# CurrentSensor.net
KiCad netlist of a schematic drawn in EAGLE
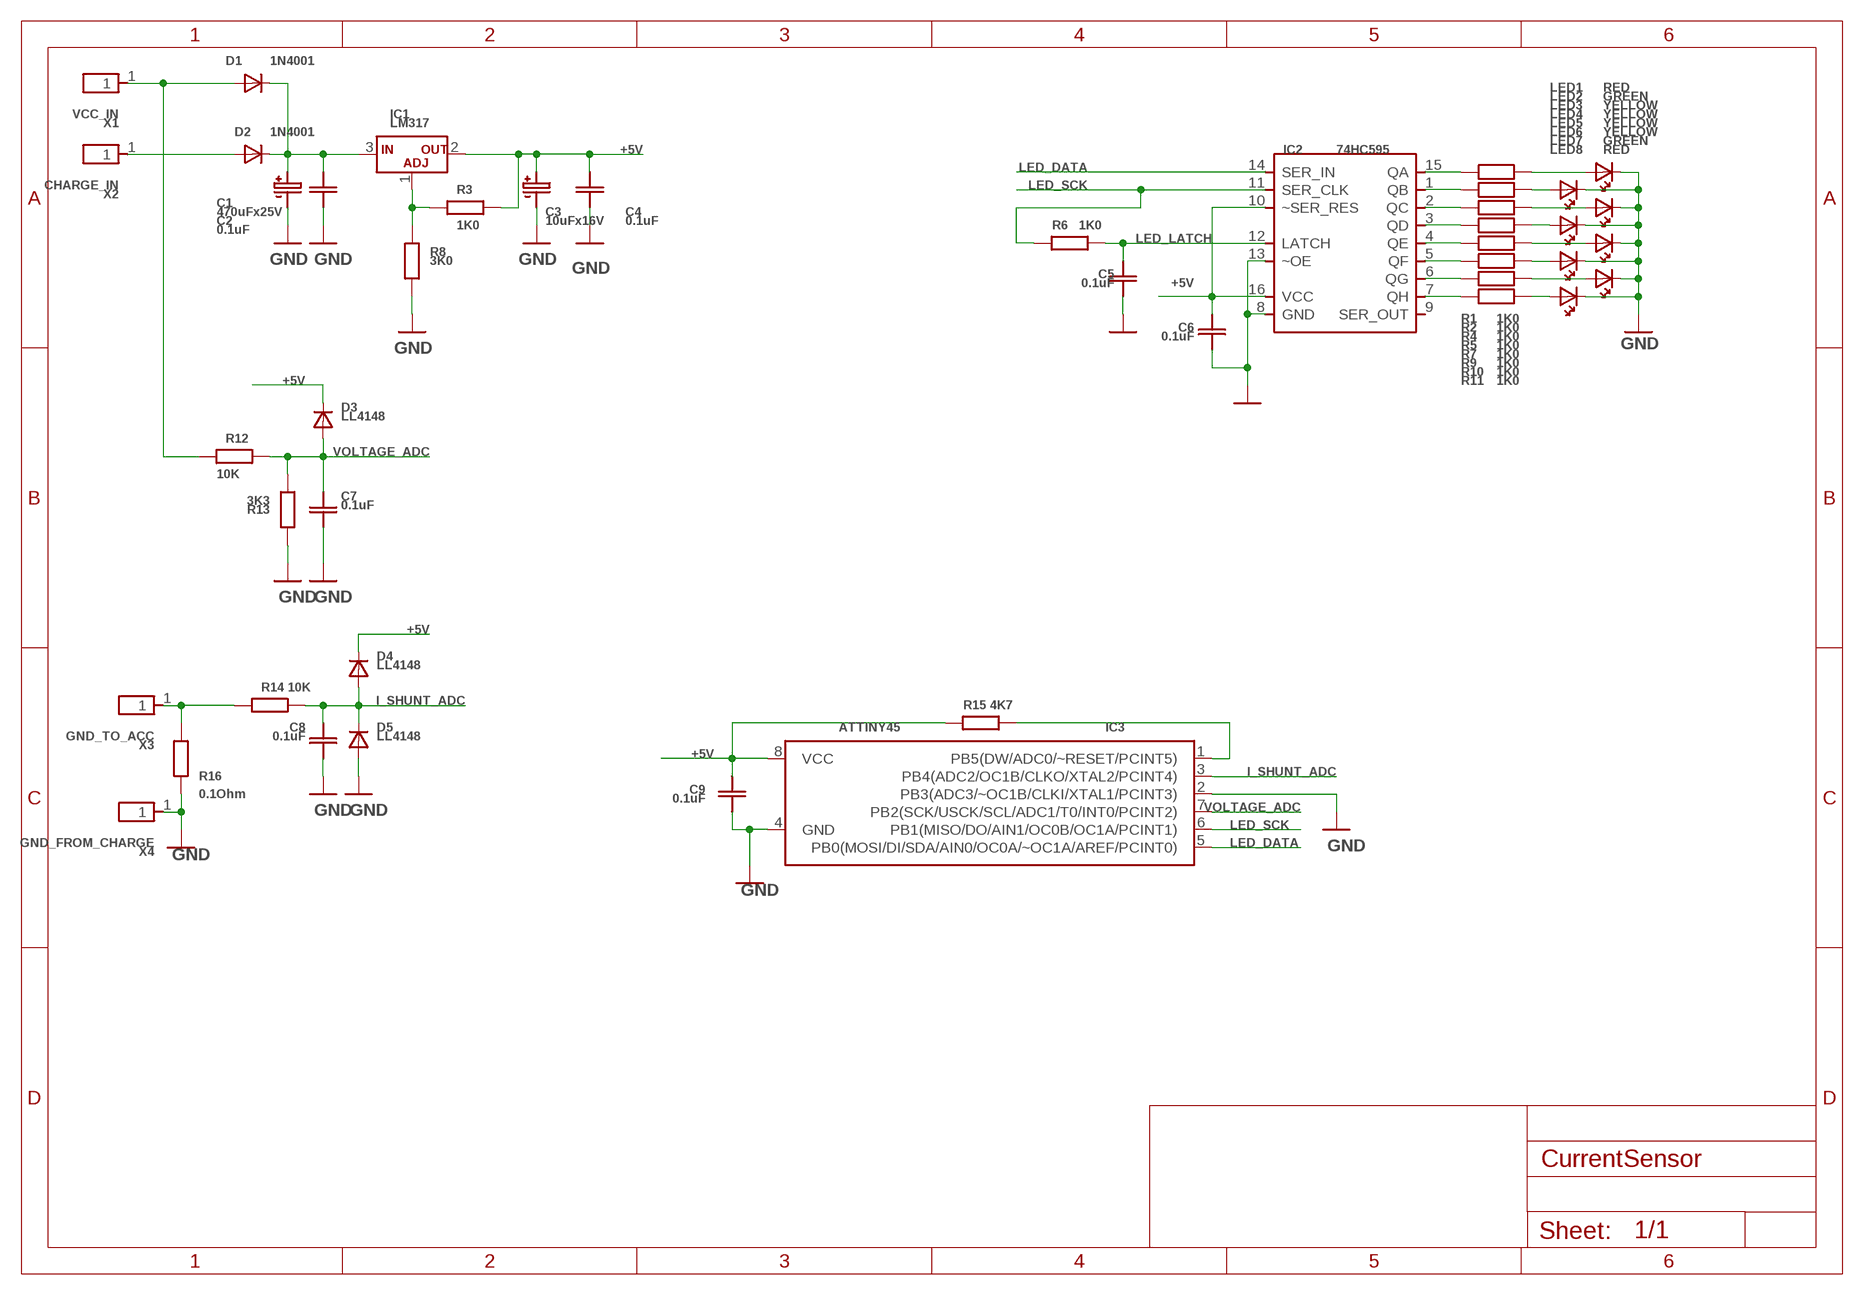
[diagram p0: schematic, sheet 1]

(export (version "E")
  (design (tool "Eeschema 10.0.6"))
  (components
    (comp (ref "C1")
      (value "470uFx25V")
      (footprint "eagle-import:CE_6.3MM")
      (libsource (lib "eagle-import") (part "CE6.3MM"))
    )
    (comp (ref "C2")
      (value "0.1uF")
      (footprint "eagle-import:RSMD_0805")
      (libsource (lib "eagle-import") (part "CSMD_0805"))
    )
    (comp (ref "C3")
      (value "10uFx16V")
      (footprint "eagle-import:CE_5.2MM")
      (libsource (lib "eagle-import") (part "CE5.2MM"))
    )
    (comp (ref "C4")
      (value "0.1uF")
      (footprint "eagle-import:RSMD_0805")
      (libsource (lib "eagle-import") (part "CSMD_0805"))
    )
    (comp (ref "C5")
      (value "0.1uF")
      (footprint "eagle-import:RSMD_0805")
      (libsource (lib "eagle-import") (part "CSMD_0805"))
    )
    (comp (ref "C6")
      (value "0.1uF")
      (footprint "eagle-import:RSMD_0805")
      (libsource (lib "eagle-import") (part "CSMD_0805"))
    )
    (comp (ref "C7")
      (value "0.1uF")
      (footprint "eagle-import:RSMD_0805")
      (libsource (lib "eagle-import") (part "CSMD_0805"))
    )
    (comp (ref "C8")
      (value "0.1uF")
      (footprint "eagle-import:RSMD_0805")
      (libsource (lib "eagle-import") (part "CSMD_0805"))
    )
    (comp (ref "C9")
      (value "0.1uF")
      (footprint "eagle-import:RSMD_0805")
      (libsource (lib "eagle-import") (part "CSMD_0805"))
    )
    (comp (ref "D1")
      (value "1N4001")
      (footprint "eagle-import:DO-41_10MM")
      (libsource (lib "eagle-import") (part "1N4001DO-41_10MM"))
    )
    (comp (ref "D2")
      (value "1N4001")
      (footprint "eagle-import:DO-41_10MM")
      (libsource (lib "eagle-import") (part "1N4001DO-41_10MM"))
    )
    (comp (ref "D3")
      (value "LL4148")
      (footprint "eagle-import:SOD-80")
      (libsource (lib "eagle-import") (part "LL4147SOD-80"))
    )
    (comp (ref "D4")
      (value "LL4148")
      (footprint "eagle-import:SOD-80")
      (libsource (lib "eagle-import") (part "LL4147SOD-80"))
    )
    (comp (ref "D5")
      (value "LL4148")
      (footprint "eagle-import:SOD-80")
      (libsource (lib "eagle-import") (part "LL4147SOD-80"))
    )
    (comp (ref "IC1")
      (value "LM317")
      (footprint "eagle-import:D2PAK")
      (libsource (lib "eagle-import") (part "LM317(D2PAK)"))
    )
    (comp (ref "IC2")
      (value "74HC595")
      (footprint "eagle-import:SOIC16")
      (libsource (lib "eagle-import") (part "74HC595(SOIC16)"))
    )
    (comp (ref "IC3")
      (value "ATTINY45")
      (footprint "eagle-import:SOIC8(0.15'')")
      (libsource (lib "eagle-import") (part "ATTINY45(SOIC8-0.15'')"))
    )
    (comp (ref "LED1")
      (value "RED")
      (footprint "eagle-import:LED3MM")
      (libsource (lib "eagle-import") (part "LED3MM"))
    )
    (comp (ref "LED2")
      (value "GREEN")
      (footprint "eagle-import:LED3MM")
      (libsource (lib "eagle-import") (part "LED3MM"))
    )
    (comp (ref "LED3")
      (value "YELLOW")
      (footprint "eagle-import:LED3MM")
      (libsource (lib "eagle-import") (part "LED3MM"))
    )
    (comp (ref "LED4")
      (value "YELLOW")
      (footprint "eagle-import:LED3MM")
      (libsource (lib "eagle-import") (part "LED3MM"))
    )
    (comp (ref "LED5")
      (value "YELLOW")
      (footprint "eagle-import:LED3MM")
      (libsource (lib "eagle-import") (part "LED3MM"))
    )
    (comp (ref "LED6")
      (value "YELLOW")
      (footprint "eagle-import:LED3MM")
      (libsource (lib "eagle-import") (part "LED3MM"))
    )
    (comp (ref "LED7")
      (value "GREEN")
      (footprint "eagle-import:LED3MM")
      (libsource (lib "eagle-import") (part "LED3MM"))
    )
    (comp (ref "LED8")
      (value "RED")
      (footprint "eagle-import:LED3MM")
      (libsource (lib "eagle-import") (part "LED3MM"))
    )
    (comp (ref "R1")
      (value "1K0")
      (footprint "eagle-import:RSMD_1206")
      (libsource (lib "eagle-import") (part "RSMD_1206"))
    )
    (comp (ref "R2")
      (value "1K0")
      (footprint "eagle-import:RSMD_0805")
      (libsource (lib "eagle-import") (part "RSMD_0805"))
    )
    (comp (ref "R3")
      (value "1K0")
      (footprint "eagle-import:RSMD_0805")
      (libsource (lib "eagle-import") (part "RSMD_0805"))
    )
    (comp (ref "R4")
      (value "1K0")
      (footprint "eagle-import:RSMD_0805")
      (libsource (lib "eagle-import") (part "RSMD_0805"))
    )
    (comp (ref "R5")
      (value "1K0")
      (footprint "eagle-import:RSMD_0805")
      (libsource (lib "eagle-import") (part "RSMD_0805"))
    )
    (comp (ref "R6")
      (value "1K0")
      (footprint "eagle-import:RSMD_0805")
      (libsource (lib "eagle-import") (part "RSMD_0805"))
    )
    (comp (ref "R7")
      (value "1K0")
      (footprint "eagle-import:RSMD_0805")
      (libsource (lib "eagle-import") (part "RSMD_0805"))
    )
    (comp (ref "R8")
      (value "3K0")
      (footprint "eagle-import:RSMD_0805")
      (libsource (lib "eagle-import") (part "RSMD_0805"))
    )
    (comp (ref "R9")
      (value "1K0")
      (footprint "eagle-import:RSMD_0805")
      (libsource (lib "eagle-import") (part "RSMD_0805"))
    )
    (comp (ref "R10")
      (value "1K0")
      (footprint "eagle-import:RSMD_0805")
      (libsource (lib "eagle-import") (part "RSMD_0805"))
    )
    (comp (ref "R11")
      (value "1K0")
      (footprint "eagle-import:RSMD_0805")
      (libsource (lib "eagle-import") (part "RSMD_0805"))
    )
    (comp (ref "R12")
      (value "10K")
      (footprint "eagle-import:RSMD_1206_BIG_GAP")
      (libsource (lib "eagle-import") (part "RSMD_1206_BIG_GAP"))
    )
    (comp (ref "R13")
      (value "3K3")
      (footprint "eagle-import:RSMD_0805")
      (libsource (lib "eagle-import") (part "RSMD_0805"))
    )
    (comp (ref "R14")
      (value "10K")
      (footprint "eagle-import:RSMD_0805")
      (libsource (lib "eagle-import") (part "RSMD_0805"))
    )
    (comp (ref "R15")
      (value "4K7")
      (footprint "eagle-import:RSMD_0805")
      (libsource (lib "eagle-import") (part "RSMD_0805"))
    )
    (comp (ref "R16")
      (value "0.1Ohm")
      (footprint "eagle-import:R_1.0W")
      (libsource (lib "eagle-import") (part "R1.0W"))
    )
    (comp (ref "X1")
      (value "VCC_IN")
      (footprint "eagle-import:PIN1X1_3.5MM_SIDE_BOARD")
      (libsource (lib "eagle-import") (part "PIN1X13.5MM_SIDE_BOARD"))
    )
    (comp (ref "X2")
      (value "CHARGE_IN")
      (footprint "eagle-import:PIN1X1_3.5MM_SIDE_BOARD")
      (libsource (lib "eagle-import") (part "PIN1X13.5MM_SIDE_BOARD"))
    )
    (comp (ref "X3")
      (value "GND_TO_ACC")
      (footprint "eagle-import:PIN1X1_3.5MM_SIDE_BOARD")
      (libsource (lib "eagle-import") (part "PIN1X13.5MM_SIDE_BOARD"))
    )
    (comp (ref "X4")
      (value "GND_FROM_CHARGE")
      (footprint "eagle-import:PIN1X1_3.5MM_SIDE_BOARD")
      (libsource (lib "eagle-import") (part "PIN1X13.5MM_SIDE_BOARD"))
    )
  )
  (nets
    (net (code "1") (name "/+5V") (class "Default")
      (node (ref "C3") (pin "PLUS") (pinfunction "PLUS_PLUS") (pintype "bidirectional"))
      (node (ref "C4") (pin "PAD_0") (pinfunction "PIN0_PAD_0") (pintype "bidirectional"))
      (node (ref "C6") (pin "PAD_0") (pinfunction "PIN0_PAD_0") (pintype "bidirectional"))
      (node (ref "C9") (pin "PAD_0") (pinfunction "PIN0_PAD_0") (pintype "bidirectional"))
      (node (ref "D3") (pin "CATHODE") (pinfunction "CATHODE_CATHODE") (pintype "passive"))
      (node (ref "D4") (pin "CATHODE") (pinfunction "CATHODE_CATHODE") (pintype "passive"))
      (node (ref "IC1") (pin "2") (pinfunction "OUT_2") (pintype "output"))
      (node (ref "IC2") (pin "10") (pinfunction "~{SER_RES}_10") (pintype "bidirectional"))
      (node (ref "IC2") (pin "16") (pinfunction "VCC_16") (pintype "bidirectional"))
      (node (ref "IC3") (pin "8") (pinfunction "VCC_8") (pintype "bidirectional"))
      (node (ref "R15") (pin "PAD_0") (pinfunction "PIN0_PAD_0") (pintype "passive"))
      (node (ref "R3") (pin "PAD_1") (pinfunction "PIN1_PAD_1") (pintype "passive"))
    )
    (net (code "2") (name "/I_SHUNT_ADC") (class "Default")
      (node (ref "C8") (pin "PAD_0") (pinfunction "PIN0_PAD_0") (pintype "bidirectional"))
      (node (ref "D4") (pin "ANODE") (pinfunction "ANODE_ANODE") (pintype "passive"))
      (node (ref "D5") (pin "CATHODE") (pinfunction "CATHODE_CATHODE") (pintype "passive"))
      (node (ref "IC3") (pin "3") (pinfunction "PB4(ADC2/OC1B/CLKO/XTAL2/PCINT4)_3") (pintype "bidirectional"))
      (node (ref "R14") (pin "PAD_1") (pinfunction "PIN1_PAD_1") (pintype "passive"))
    )
    (net (code "3") (name "/LED_DATA") (class "Default")
      (node (ref "IC2") (pin "14") (pinfunction "SER_IN_14") (pintype "bidirectional"))
      (node (ref "IC3") (pin "5") (pinfunction "PB0(MOSI/DI/SDA/AIN0/OC0A/~{OC1A/AREF/PCINT0})_5") (pintype "bidirectional"))
    )
    (net (code "4") (name "/LED_LATCH") (class "Default")
      (node (ref "C5") (pin "PAD_0") (pinfunction "PIN0_PAD_0") (pintype "bidirectional"))
      (node (ref "IC2") (pin "12") (pinfunction "LATCH_12") (pintype "bidirectional"))
      (node (ref "R6") (pin "PAD_1") (pinfunction "PIN1_PAD_1") (pintype "passive"))
    )
    (net (code "5") (name "/LED_SCK") (class "Default")
      (node (ref "IC2") (pin "11") (pinfunction "SER_CLK_11") (pintype "bidirectional"))
      (node (ref "IC3") (pin "6") (pinfunction "PB1(MISO/DO/AIN1/OC0B/OC1A/PCINT1)_6") (pintype "bidirectional"))
      (node (ref "R6") (pin "PAD_0") (pinfunction "PIN0_PAD_0") (pintype "passive"))
    )
    (net (code "6") (name "/VOLTAGE_ADC") (class "Default")
      (node (ref "C7") (pin "PAD_0") (pinfunction "PIN0_PAD_0") (pintype "bidirectional"))
      (node (ref "D3") (pin "ANODE") (pinfunction "ANODE_ANODE") (pintype "passive"))
      (node (ref "IC3") (pin "7") (pinfunction "PB2(SCK/USCK/SCL/ADC1/T0/INT0/PCINT2)_7") (pintype "bidirectional"))
      (node (ref "R12") (pin "PAD_1") (pinfunction "PIN1_PAD_1") (pintype "passive"))
      (node (ref "R13") (pin "PAD_1") (pinfunction "PIN1_PAD_1") (pintype "passive"))
    )
    (net (code "7") (name "GND") (class "Default")
      (node (ref "C1") (pin "MINUS") (pinfunction "MINUS_MINUS") (pintype "bidirectional"))
      (node (ref "C2") (pin "PAD_1") (pinfunction "PIN1_PAD_1") (pintype "bidirectional"))
      (node (ref "C3") (pin "MINUS") (pinfunction "MINUS_MINUS") (pintype "bidirectional"))
      (node (ref "C4") (pin "PAD_1") (pinfunction "PIN1_PAD_1") (pintype "bidirectional"))
      (node (ref "C5") (pin "PAD_1") (pinfunction "PIN1_PAD_1") (pintype "bidirectional"))
      (node (ref "C6") (pin "PAD_1") (pinfunction "PIN1_PAD_1") (pintype "bidirectional"))
      (node (ref "C7") (pin "PAD_1") (pinfunction "PIN1_PAD_1") (pintype "bidirectional"))
      (node (ref "C8") (pin "PAD_1") (pinfunction "PIN1_PAD_1") (pintype "bidirectional"))
      (node (ref "C9") (pin "PAD_1") (pinfunction "PIN1_PAD_1") (pintype "bidirectional"))
      (node (ref "D5") (pin "ANODE") (pinfunction "ANODE_ANODE") (pintype "passive"))
      (node (ref "IC2") (pin "13") (pinfunction "~{OE}_13") (pintype "bidirectional"))
      (node (ref "IC2") (pin "8") (pinfunction "GND_8") (pintype "bidirectional"))
      (node (ref "IC3") (pin "2") (pinfunction "PB3(ADC3/~{OC1B/CLKI/XTAL1/PCINT3})_2") (pintype "bidirectional"))
      (node (ref "IC3") (pin "4") (pinfunction "GND_4") (pintype "bidirectional"))
      (node (ref "LED1") (pin "CATHODE") (pinfunction "CATHODE_CATHODE") (pintype "passive"))
      (node (ref "LED2") (pin "CATHODE") (pinfunction "CATHODE_CATHODE") (pintype "passive"))
      (node (ref "LED3") (pin "CATHODE") (pinfunction "CATHODE_CATHODE") (pintype "passive"))
      (node (ref "LED4") (pin "CATHODE") (pinfunction "CATHODE_CATHODE") (pintype "passive"))
      (node (ref "LED5") (pin "CATHODE") (pinfunction "CATHODE_CATHODE") (pintype "passive"))
      (node (ref "LED6") (pin "CATHODE") (pinfunction "CATHODE_CATHODE") (pintype "passive"))
      (node (ref "LED7") (pin "CATHODE") (pinfunction "CATHODE_CATHODE") (pintype "passive"))
      (node (ref "LED8") (pin "CATHODE") (pinfunction "CATHODE_CATHODE") (pintype "passive"))
      (node (ref "R13") (pin "PAD_0") (pinfunction "PIN0_PAD_0") (pintype "passive"))
      (node (ref "R16") (pin "PAD1") (pinfunction "PIN1_PAD1") (pintype "passive"))
      (node (ref "R8") (pin "PAD_0") (pinfunction "PIN0_PAD_0") (pintype "passive"))
      (node (ref "X4") (pin "1") (pinfunction "1_1") (pintype "bidirectional"))
    )
    (net (code "8") (name "Net-(C2-PIN0)") (class "Default")
      (node (ref "C1") (pin "PLUS") (pinfunction "PLUS_PLUS") (pintype "bidirectional"))
      (node (ref "C2") (pin "PAD_0") (pinfunction "PIN0_PAD_0") (pintype "bidirectional"))
      (node (ref "D1") (pin "CATHODE") (pinfunction "CATHODE_CATHODE") (pintype "passive"))
      (node (ref "D2") (pin "CATHODE") (pinfunction "CATHODE_CATHODE") (pintype "passive"))
      (node (ref "IC1") (pin "3") (pinfunction "IN_3") (pintype "input"))
    )
    (net (code "9") (name "Net-(D2-PadANODE)") (class "Default")
      (node (ref "D2") (pin "ANODE") (pinfunction "ANODE_ANODE") (pintype "passive"))
      (node (ref "X2") (pin "1") (pinfunction "1_1") (pintype "bidirectional"))
    )
    (net (code "10") (name "Net-(IC1-ADJ)") (class "Default")
      (node (ref "IC1") (pin "1") (pinfunction "ADJ_1") (pintype "input"))
      (node (ref "R3") (pin "PAD_0") (pinfunction "PIN0_PAD_0") (pintype "passive"))
      (node (ref "R8") (pin "PAD_1") (pinfunction "PIN1_PAD_1") (pintype "passive"))
    )
    (net (code "11") (name "Net-(IC2-QA)") (class "Default")
      (node (ref "IC2") (pin "15") (pinfunction "QA_15") (pintype "bidirectional"))
      (node (ref "R1") (pin "PAD_0") (pinfunction "PIN0_PAD_0") (pintype "passive"))
    )
    (net (code "12") (name "Net-(IC2-QB)") (class "Default")
      (node (ref "IC2") (pin "1") (pinfunction "QB_1") (pintype "bidirectional"))
      (node (ref "R2") (pin "PAD_0") (pinfunction "PIN0_PAD_0") (pintype "passive"))
    )
    (net (code "13") (name "Net-(IC2-QC)") (class "Default")
      (node (ref "IC2") (pin "2") (pinfunction "QC_2") (pintype "bidirectional"))
      (node (ref "R4") (pin "PAD_0") (pinfunction "PIN0_PAD_0") (pintype "passive"))
    )
    (net (code "14") (name "Net-(IC2-QD)") (class "Default")
      (node (ref "IC2") (pin "3") (pinfunction "QD_3") (pintype "bidirectional"))
      (node (ref "R5") (pin "PAD_0") (pinfunction "PIN0_PAD_0") (pintype "passive"))
    )
    (net (code "15") (name "Net-(IC2-QE)") (class "Default")
      (node (ref "IC2") (pin "4") (pinfunction "QE_4") (pintype "bidirectional"))
      (node (ref "R7") (pin "PAD_0") (pinfunction "PIN0_PAD_0") (pintype "passive"))
    )
    (net (code "16") (name "Net-(IC2-QF)") (class "Default")
      (node (ref "IC2") (pin "5") (pinfunction "QF_5") (pintype "bidirectional"))
      (node (ref "R9") (pin "PAD_0") (pinfunction "PIN0_PAD_0") (pintype "passive"))
    )
    (net (code "17") (name "Net-(IC2-QG)") (class "Default")
      (node (ref "IC2") (pin "6") (pinfunction "QG_6") (pintype "bidirectional"))
      (node (ref "R10") (pin "PAD_0") (pinfunction "PIN0_PAD_0") (pintype "passive"))
    )
    (net (code "18") (name "Net-(IC2-QH)") (class "Default")
      (node (ref "IC2") (pin "7") (pinfunction "QH_7") (pintype "bidirectional"))
      (node (ref "R11") (pin "PAD_0") (pinfunction "PIN0_PAD_0") (pintype "passive"))
    )
    (net (code "19") (name "Net-(IC3-PB5(DW{slash}ADC0{slash}~{RESET{slash}PCINT5}))") (class "Default")
      (node (ref "IC3") (pin "1") (pinfunction "PB5(DW/ADC0/~{RESET/PCINT5})_1") (pintype "bidirectional"))
      (node (ref "R15") (pin "PAD_1") (pinfunction "PIN1_PAD_1") (pintype "passive"))
    )
    (net (code "20") (name "Net-(R1-PIN1)") (class "Default")
      (node (ref "LED1") (pin "ANODE") (pinfunction "ANODE_ANODE") (pintype "passive"))
      (node (ref "R1") (pin "PAD_1") (pinfunction "PIN1_PAD_1") (pintype "passive"))
    )
    (net (code "21") (name "Net-(R2-PIN1)") (class "Default")
      (node (ref "LED2") (pin "ANODE") (pinfunction "ANODE_ANODE") (pintype "passive"))
      (node (ref "R2") (pin "PAD_1") (pinfunction "PIN1_PAD_1") (pintype "passive"))
    )
    (net (code "22") (name "Net-(R4-PIN1)") (class "Default")
      (node (ref "LED3") (pin "ANODE") (pinfunction "ANODE_ANODE") (pintype "passive"))
      (node (ref "R4") (pin "PAD_1") (pinfunction "PIN1_PAD_1") (pintype "passive"))
    )
    (net (code "23") (name "Net-(R5-PIN1)") (class "Default")
      (node (ref "LED4") (pin "ANODE") (pinfunction "ANODE_ANODE") (pintype "passive"))
      (node (ref "R5") (pin "PAD_1") (pinfunction "PIN1_PAD_1") (pintype "passive"))
    )
    (net (code "24") (name "Net-(R7-PIN1)") (class "Default")
      (node (ref "LED5") (pin "ANODE") (pinfunction "ANODE_ANODE") (pintype "passive"))
      (node (ref "R7") (pin "PAD_1") (pinfunction "PIN1_PAD_1") (pintype "passive"))
    )
    (net (code "25") (name "Net-(R9-PIN1)") (class "Default")
      (node (ref "LED6") (pin "ANODE") (pinfunction "ANODE_ANODE") (pintype "passive"))
      (node (ref "R9") (pin "PAD_1") (pinfunction "PIN1_PAD_1") (pintype "passive"))
    )
    (net (code "26") (name "Net-(R10-PIN1)") (class "Default")
      (node (ref "LED7") (pin "ANODE") (pinfunction "ANODE_ANODE") (pintype "passive"))
      (node (ref "R10") (pin "PAD_1") (pinfunction "PIN1_PAD_1") (pintype "passive"))
    )
    (net (code "27") (name "Net-(R11-PIN1)") (class "Default")
      (node (ref "LED8") (pin "ANODE") (pinfunction "ANODE_ANODE") (pintype "passive"))
      (node (ref "R11") (pin "PAD_1") (pinfunction "PIN1_PAD_1") (pintype "passive"))
    )
    (net (code "28") (name "Net-(R12-PIN0)") (class "Default")
      (node (ref "D1") (pin "ANODE") (pinfunction "ANODE_ANODE") (pintype "passive"))
      (node (ref "R12") (pin "PAD_0") (pinfunction "PIN0_PAD_0") (pintype "passive"))
      (node (ref "X1") (pin "1") (pinfunction "1_1") (pintype "bidirectional"))
    )
    (net (code "29") (name "Net-(R14-PIN0)") (class "Default")
      (node (ref "R14") (pin "PAD_0") (pinfunction "PIN0_PAD_0") (pintype "passive"))
      (node (ref "R16") (pin "PAD_0") (pinfunction "PIN0_PAD_0") (pintype "passive"))
      (node (ref "X3") (pin "1") (pinfunction "1_1") (pintype "bidirectional"))
    )
    (net (code "30") (name "unconnected-(IC2-SER_OUT-Pad9)") (class "Default")
      (node (ref "IC2") (pin "9") (pinfunction "SER_OUT_9") (pintype "bidirectional"))
    )
  )
)
